# Converter_12V-5V.net
KiCad netlist of a schematic drawn in Altium Designer
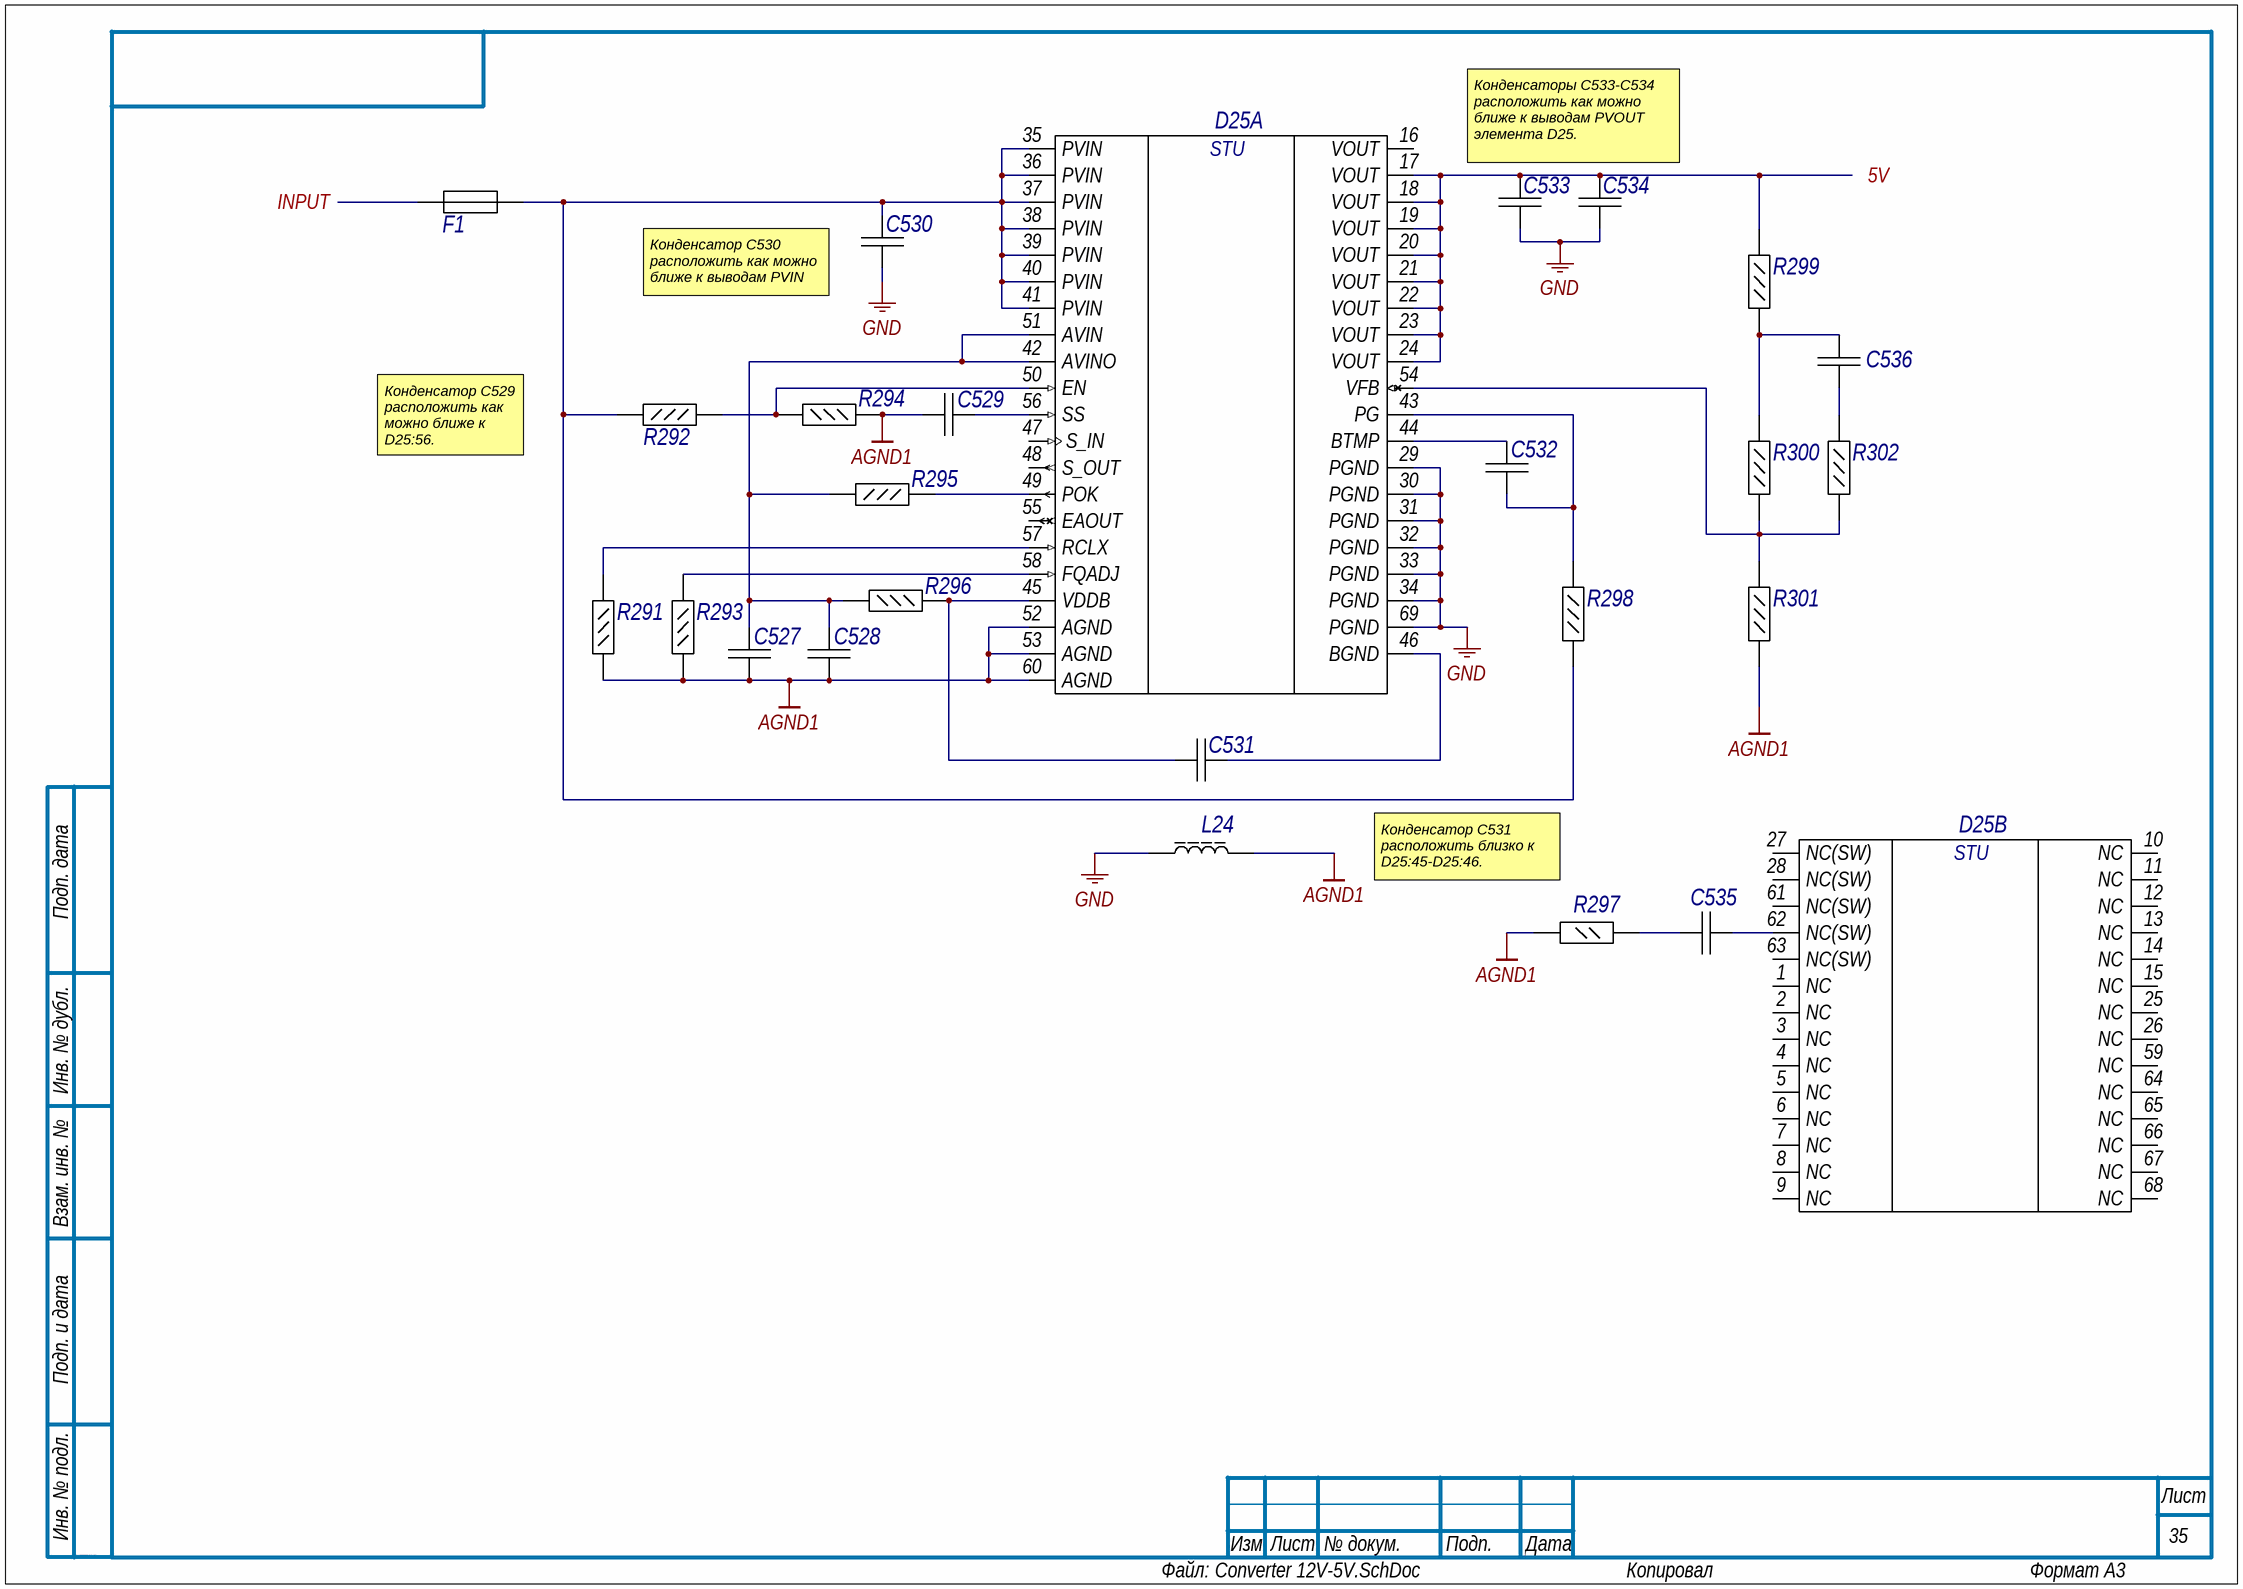
[diagram p0: Converter 12V-5V.SchDoc]

(export (version "E")
  (design (tool "Eeschema 10.0.6"))
  (components
    (comp (ref "C527")
      (value "CGB2A1X5R1E105K033BC")
      (footprint "CAPC1005X33X10LL5")
      (description "Chip Capacitor, 1 uF, +/- 10%, 25 V, -55 to 85 degC, 0402 (1005 Metric), RoHS, Tape and Reel")
      (fields (field (name "TOLERANCE") "10%"))
      (libsource (lib "MiniPC DB") (part "CAP_NP"))
    )
    (comp (ref "C528")
      (value "CGB2A1X5R1E105K033BC")
      (footprint "CAPC1005X33X10LL5")
      (description "Chip Capacitor, 1 uF, +/- 10%, 25 V, -55 to 85 degC, 0402 (1005 Metric), RoHS, Tape and Reel")
      (fields (field (name "TOLERANCE") "10%"))
      (libsource (lib "MiniPC DB") (part "CAP_NP"))
    )
    (comp (ref "C529")
      (value "GRM155R71E473KA88D")
      (footprint "CAPC1005X55X25NL05T10")
      (description "Chip Capacitor, 47 nF, +/- 10%, 25 V, -55 to 125 degC, 0402 (1005 Metric), RoHS, Tape and Reel")
      (fields (field (name "TOLERANCE") "10%") (field (name "MANUFACTURER") "Basic Passives"))
      (libsource (lib "MiniPC DB") (part "CAP_NP"))
    )
    (comp (ref "C530")
      (value "GRM31CR61E226KE15L")
      (footprint "CAPC3216X180X55ML20T25")
      (description "Chip Capacitor, 22 uF, +/- 10%, 25 V, -55 to 85 degC, 1206 (3216 Metric), RoHS, Tape and Reel")
      (fields (field (name "TOLERANCE") "10%"))
      (libsource (lib "MiniPC DB") (part "CAP_NP"))
    )
    (comp (ref "C531")
      (value "GRM155R61A224KE19D")
      (footprint "CAPC1005X55X25NL05T10")
      (description "Chip Capacitor, 220 nF, +/- 10%, 10 V, -55 to 85 degC, 0402 (1005 Metric), RoHS, Tape and Reel")
      (fields (field (name "TOLERANCE") "10%") (field (name "MANUFACTURER") "Basic Passives"))
      (libsource (lib "MiniPC DB") (part "CAP_NP"))
    )
    (comp (ref "C532")
      (value "GRM155R71E223KA61D")
      (footprint "CAPC1005X55X25ML05T10")
      (description "Chip Capacitor, 22 nF, +/- 10%, 25 V, -55 to 125 degC, 0402 (1005 Metric), RoHS, Tape and Reel")
      (fields (field (name "TOLERANCE") "10%") (field (name "MANUFACTURER") "Basic Passives"))
      (libsource (lib "MiniPC DB") (part "CAP_NP"))
    )
    (comp (ref "C533")
      (value "C3216X5R1A476M160AB")
      (footprint "CAPC3216X180X20ML20")
      (description "Chip Capacitor, 47 uF, +/- 20%, 10 V, -55 to 85 degC, 1206 (3216 Metric), RoHS, Tape and Reel")
      (fields (field (name "TOLERANCE") "20%"))
      (libsource (lib "MiniPC DB") (part "CAP_NP"))
    )
    (comp (ref "C534")
      (value "C3216X5R1A476M160AB")
      (footprint "CAPC3216X180X20ML20")
      (description "Chip Capacitor, 47 uF, +/- 20%, 10 V, -55 to 85 degC, 1206 (3216 Metric), RoHS, Tape and Reel")
      (fields (field (name "TOLERANCE") "20%"))
      (libsource (lib "MiniPC DB") (part "CAP_NP"))
    )
    (comp (ref "C535")
      (value "GRM155R71H681KA01D")
      (footprint "CAPC1005X55X25ML05T10")
      (description "Chip Capacitor, 680 pF, +/- 10%, 50 V, -55 to 125 degC, 0402 (1005 Metric), RoHS, Tape and Reel")
      (fields (field (name "TOLERANCE") "10%") (field (name "MANUFACTURER") "Basic Passives"))
      (libsource (lib "MiniPC DB") (part "CAP_NP"))
    )
    (comp (ref "C536")
      (value "GRM1535C1H560JDD5D")
      (footprint "CAPC1005X33X20ML05T10")
      (description "Chip Capacitor, 56 pF, +/- 5%, 50 V, -55 to 125 degC, 0402 (1005 Metric), RoHS, Tape and Reel")
      (fields (field (name "TOLERANCE") "5%") (field (name "MANUFACTURER") "Basic Passives"))
      (libsource (lib "MiniPC DB") (part "CAP_NP"))
    )
    (comp (ref "D25")
      (value "EN2342QI")
      (footprint "ALTR-QFN-68_A-305_D1-210_V")
      (libsource (lib "MiniPC DB") (part "EN2342QI"))
    )
    (comp (ref "F1")
      (value "154001")
      (footprint "LFUS-0154001.DR_V")
      (libsource (lib "MiniPC DB") (part "FUSE"))
    )
    (comp (ref "L24")
      (value "742792609")
      (footprint "SMD-0603")
      (description "SMD EMI Suppression Ferrite Bead WE-CBF, Z = 30 Ohm")
      (libsource (lib "MiniPC DB") (part "Choke"))
    )
    (comp (ref "R291")
      (value "ERJ-2RKF6812X")
      (footprint "RESC1005X40X25LL05T05")
      (description "Chip Resistor, 68.1 KOhm, +/- 1%, 100 mW, -55 to 155 degC, 0402 (1005 Metric), RoHS, Tape and Reel")
      (fields (field (name "TOLERANCE") "1%") (field (name "MANUFACTURER") "Basic Passives"))
      (libsource (lib "MiniPC DB") (part "RES-0.05"))
    )
    (comp (ref "R292")
      (value "ERJ-2RKF4992X")
      (footprint "RESC1005X40X25LL05T05")
      (description "Chip Resistor, 49.9 KOhm, +/- 1%, 100 mW, -55 to 155 degC, 0402 (1005 Metric), RoHS, Tape and Reel")
      (fields (field (name "TOLERANCE") "1%") (field (name "MANUFACTURER") "Basic Passives"))
      (libsource (lib "MiniPC DB") (part "RES-0.05"))
    )
    (comp (ref "R293")
      (value "CRCW040230K1FKED")
      (footprint "RESC1005X40X25LL05T05")
      (description "Chip Resistor, 30.1 KOhm, +/- 1%, 63 mW, -55 to 155 degC, 0402 (1005 Metric), RoHS, Tape and Reel")
      (fields (field (name "TOLERANCE") "1%") (field (name "MANUFACTURER") "Basic Passives"))
      (libsource (lib "MiniPC DB") (part "RES-0.05"))
    )
    (comp (ref "R294")
      (value "ERJ-2RKF1002X")
      (footprint "RESC1005X40X25LL05T05")
      (description "Chip Resistor, 10 KOhm, +/- 1%, 100 mW, -55 to 155 degC, 0402 (1005 Metric), RoHS, Tape and Reel")
      (fields (field (name "TOLERANCE") "1%") (field (name "MANUFACTURER") "Basic Passives"))
      (libsource (lib "") (part "RES-0.05_3"))
    )
    (comp (ref "R295")
      (value "ERJ-2RKF1003X")
      (footprint "RESC1005X40X25LL05T05")
      (description "Chip Resistor, 100 KOhm, +/- 1%, 100 mW, -55 to 155 degC, 0402 (1005 Metric), RoHS, Tape and Reel")
      (fields (field (name "TOLERANCE") "1%") (field (name "MANUFACTURER") "Basic Passives"))
      (libsource (lib "") (part "RES-0.05_2"))
    )
    (comp (ref "R296")
      (value "ERJ-2RKF4751X")
      (footprint "RESC1005X40X25LL05T05")
      (description "Chip Resistor, 4.75 KOhm, +/- 1%, 100 mW, -55 to 155 degC, 0402 (1005 Metric), RoHS, Tape and Reel")
      (fields (field (name "TOLERANCE") "1%") (field (name "MANUFACTURER") "Basic Passives"))
      (libsource (lib "") (part "RES-0.05_1"))
    )
    (comp (ref "R297")
      (value "ERJ-6RQF4R7V")
      (footprint "RESC2013X70X40LL20T20")
      (description "Chip Resistor, 4.7 Ohm, +/- 1%, 125 mW, -55 to 125 degC, 0805 (2012 Metric), RoHS, Tape and Reel")
      (fields (field (name "TOLERANCE") "1%"))
      (libsource (lib "MiniPC DB") (part "RES-0.125"))
    )
    (comp (ref "R298")
      (value "ERJ-2GEJ561x")
      (footprint "RESC1005X40X25LL05T05")
      (description "Chip Resistor, 560 Ohm, +/- 5%, 100 mW, -55 to 155 degC, 0402 (1005 Metric), RoHS, Tape and Reel")
      (fields (field (name "TOLERANCE") "5%") (field (name "MANUFACTURER") "Basic Passives"))
      (libsource (lib "") (part "RES-0.05_1"))
    )
    (comp (ref "R299")
      (value "ERJ-2GE0R00X")
      (footprint "RESC1005X40X25LL05T05")
      (description "Chip Resistor, 0 mOhm, +/- 5%, 100 mW, -55 to 155 degC, 0402 (1005 Metric), RoHS, Tape and Reel")
      (fields (field (name "TOLERANCE") "5%") (field (name "MANUFACTURER") "Basic Passives"))
      (libsource (lib "") (part "RES-0.05_1"))
    )
    (comp (ref "R300")
      (value "ERJ-2RKF8062X")
      (footprint "RESC1005X40X25LL05T05")
      (description "Chip Resistor, 80.6 KOhm, +/- 1%, 100 mW, -55 to 155 degC, 0402 (1005 Metric), RoHS, Tape and Reel")
      (fields (field (name "TOLERANCE") "1%") (field (name "MANUFACTURER") "Basic Passives"))
      (libsource (lib "") (part "RES-0.05_1"))
    )
    (comp (ref "R301")
      (value "ERJ-2RKF1432X")
      (footprint "RESC1005X40X25LL05T05")
      (description "Chip Resistor, 14.3 KOhm, +/- 1%, 100 mW, -55 to 155 degC, 0402 (1005 Metric), RoHS, Tape and Reel")
      (fields (field (name "TOLERANCE") "1%") (field (name "MANUFACTURER") "Basic Passives"))
      (libsource (lib "") (part "RES-0.05_1"))
    )
    (comp (ref "R302")
      (value "ERJ-2RKF1002X")
      (footprint "RESC1005X40X25LL05T05")
      (description "Chip Resistor, 10 KOhm, +/- 1%, 100 mW, -55 to 155 degC, 0402 (1005 Metric), RoHS, Tape and Reel")
      (fields (field (name "TOLERANCE") "1%") (field (name "MANUFACTURER") "Basic Passives"))
      (libsource (lib "") (part "RES-0.05_1"))
    )
  )
  (nets
    (net (code "1") (name "/5V") (class "Default")
      (node (ref "C533") (pin "2") (pinfunction "2_2") (pintype "passive"))
      (node (ref "C534") (pin "2") (pinfunction "2_2") (pintype "passive"))
      (node (ref "D25") (pin "17") (pinfunction "VOUT_17") (pintype "power_in"))
      (node (ref "D25") (pin "18") (pinfunction "VOUT_18") (pintype "power_in"))
      (node (ref "D25") (pin "19") (pinfunction "VOUT_19") (pintype "power_in"))
      (node (ref "D25") (pin "20") (pinfunction "VOUT_20") (pintype "power_in"))
      (node (ref "D25") (pin "21") (pinfunction "VOUT_21") (pintype "power_in"))
      (node (ref "D25") (pin "22") (pinfunction "VOUT_22") (pintype "power_in"))
      (node (ref "D25") (pin "23") (pinfunction "VOUT_23") (pintype "power_in"))
      (node (ref "D25") (pin "24") (pinfunction "VOUT_24") (pintype "power_in"))
      (node (ref "R299") (pin "2") (pinfunction "2_2") (pintype "passive"))
    )
    (net (code "2") (name "/INPUT") (class "Default")
      (node (ref "F1") (pin "2") (pinfunction "2_2") (pintype "passive"))
    )
    (net (code "3") (name "AGND1") (class "Default")
      (node (ref "C527") (pin "2") (pinfunction "2_2") (pintype "passive"))
      (node (ref "C528") (pin "1") (pinfunction "1_1") (pintype "passive"))
      (node (ref "C529") (pin "1") (pinfunction "1_1") (pintype "passive"))
      (node (ref "D25") (pin "52") (pinfunction "AGND_52") (pintype "power_in"))
      (node (ref "D25") (pin "53") (pinfunction "AGND_53") (pintype "power_in"))
      (node (ref "D25") (pin "60") (pinfunction "AGND_60") (pintype "power_in"))
      (node (ref "L24") (pin "2") (pinfunction "2_2") (pintype "passive"))
      (node (ref "R291") (pin "1") (pinfunction "1_1") (pintype "passive"))
      (node (ref "R293") (pin "1") (pinfunction "1_1") (pintype "passive"))
      (node (ref "R294") (pin "1") (pinfunction "1_1") (pintype "passive"))
      (node (ref "R297") (pin "1") (pinfunction "1_1") (pintype "passive"))
      (node (ref "R301") (pin "1") (pinfunction "1_1") (pintype "passive"))
    )
    (net (code "4") (name "GND") (class "Default")
      (node (ref "C530") (pin "1") (pinfunction "1_1") (pintype "passive"))
      (node (ref "C533") (pin "1") (pinfunction "1_1") (pintype "passive"))
      (node (ref "C534") (pin "1") (pinfunction "1_1") (pintype "passive"))
      (node (ref "D25") (pin "29") (pinfunction "PGND_29") (pintype "power_in"))
      (node (ref "D25") (pin "30") (pinfunction "PGND_30") (pintype "power_in"))
      (node (ref "D25") (pin "31") (pinfunction "PGND_31") (pintype "power_in"))
      (node (ref "D25") (pin "32") (pinfunction "PGND_32") (pintype "power_in"))
      (node (ref "D25") (pin "33") (pinfunction "PGND_33") (pintype "power_in"))
      (node (ref "D25") (pin "34") (pinfunction "PGND_34") (pintype "power_in"))
      (node (ref "D25") (pin "69") (pinfunction "PGND_69") (pintype "power_in"))
      (node (ref "L24") (pin "1") (pinfunction "1_1") (pintype "passive"))
    )
    (net (code "5") (name "Net-(C530-Pad2)") (class "Default")
      (node (ref "C530") (pin "2") (pinfunction "2_2") (pintype "passive"))
      (node (ref "D25") (pin "35") (pinfunction "PVIN_35") (pintype "power_in"))
      (node (ref "D25") (pin "36") (pinfunction "PVIN_36") (pintype "power_in"))
      (node (ref "D25") (pin "37") (pinfunction "PVIN_37") (pintype "power_in"))
      (node (ref "D25") (pin "38") (pinfunction "PVIN_38") (pintype "power_in"))
      (node (ref "D25") (pin "39") (pinfunction "PVIN_39") (pintype "power_in"))
      (node (ref "D25") (pin "40") (pinfunction "PVIN_40") (pintype "power_in"))
      (node (ref "D25") (pin "41") (pinfunction "PVIN_41") (pintype "power_in"))
      (node (ref "F1") (pin "1") (pinfunction "1_1") (pintype "passive"))
      (node (ref "R292") (pin "1") (pinfunction "1_1") (pintype "passive"))
      (node (ref "R298") (pin "1") (pinfunction "1_1") (pintype "passive"))
    )
    (net (code "6") (name "Net-(C535-Pad1)") (class "Default")
      (node (ref "C535") (pin "1") (pinfunction "1_1") (pintype "passive"))
      (node (ref "R297") (pin "2") (pinfunction "2_2") (pintype "passive"))
    )
    (net (code "7") (name "Net-(C535-Pad2)") (class "Default")
      (node (ref "C535") (pin "2") (pinfunction "2_2") (pintype "passive"))
      (node (ref "D25") (pin "62") (pinfunction "NC(SW)_62") (pintype "passive"))
    )
    (net (code "8") (name "Net-(C536-Pad1)") (class "Default")
      (node (ref "C536") (pin "1") (pinfunction "1_1") (pintype "passive"))
      (node (ref "R302") (pin "2") (pinfunction "2_2") (pintype "passive"))
    )
    (net (code "9") (name "Net-(C536-Pad2)") (class "Default")
      (node (ref "C536") (pin "2") (pinfunction "2_2") (pintype "passive"))
      (node (ref "R299") (pin "1") (pinfunction "1_1") (pintype "passive"))
      (node (ref "R300") (pin "2") (pinfunction "2_2") (pintype "passive"))
    )
    (net (code "10") (name "Net-(D25A-AVIN)") (class "Default")
      (node (ref "C527") (pin "1") (pinfunction "1_1") (pintype "passive"))
      (node (ref "C528") (pin "2") (pinfunction "2_2") (pintype "passive"))
      (node (ref "D25") (pin "42") (pinfunction "AVINO_42") (pintype "power_in"))
      (node (ref "D25") (pin "51") (pinfunction "AVIN_51") (pintype "power_in"))
      (node (ref "R295") (pin "2") (pinfunction "2_2") (pintype "passive"))
      (node (ref "R296") (pin "1") (pinfunction "1_1") (pintype "passive"))
    )
    (net (code "11") (name "Net-(D25A-BGND)") (class "Default")
      (node (ref "C531") (pin "1") (pinfunction "1_1") (pintype "passive"))
      (node (ref "D25") (pin "46") (pinfunction "BGND_46") (pintype "power_in"))
    )
    (net (code "12") (name "Net-(D25A-BTMP)") (class "Default")
      (node (ref "C532") (pin "1") (pinfunction "1_1") (pintype "passive"))
      (node (ref "D25") (pin "44") (pinfunction "BTMP_44") (pintype "power_in"))
    )
    (net (code "13") (name "Net-(D25A-EN)") (class "Default")
      (node (ref "D25") (pin "50") (pinfunction "EN_50") (pintype "input"))
      (node (ref "R292") (pin "2") (pinfunction "2_2") (pintype "passive"))
      (node (ref "R294") (pin "2") (pinfunction "2_2") (pintype "passive"))
    )
    (net (code "14") (name "Net-(D25A-FQADJ)") (class "Default")
      (node (ref "D25") (pin "58") (pinfunction "FQADJ_58") (pintype "input"))
      (node (ref "R293") (pin "2") (pinfunction "2_2") (pintype "passive"))
    )
    (net (code "15") (name "Net-(D25A-PG)") (class "Default")
      (node (ref "C532") (pin "2") (pinfunction "2_2") (pintype "passive"))
      (node (ref "D25") (pin "43") (pinfunction "PG_43") (pintype "passive"))
      (node (ref "R298") (pin "2") (pinfunction "2_2") (pintype "passive"))
    )
    (net (code "16") (name "Net-(D25A-POK)") (class "Default")
      (node (ref "D25") (pin "49") (pinfunction "POK_49") (pintype "open_collector"))
      (node (ref "R295") (pin "1") (pinfunction "1_1") (pintype "passive"))
    )
    (net (code "17") (name "Net-(D25A-RCLX)") (class "Default")
      (node (ref "D25") (pin "57") (pinfunction "RCLX_57") (pintype "input"))
      (node (ref "R291") (pin "2") (pinfunction "2_2") (pintype "passive"))
    )
    (net (code "18") (name "Net-(D25A-SS)") (class "Default")
      (node (ref "C529") (pin "2") (pinfunction "2_2") (pintype "passive"))
      (node (ref "D25") (pin "56") (pinfunction "SS_56") (pintype "input"))
    )
    (net (code "19") (name "Net-(D25A-VDDB)") (class "Default")
      (node (ref "C531") (pin "2") (pinfunction "2_2") (pintype "passive"))
      (node (ref "D25") (pin "45") (pinfunction "VDDB_45") (pintype "power_in"))
      (node (ref "R296") (pin "2") (pinfunction "2_2") (pintype "passive"))
    )
    (net (code "20") (name "Net-(D25A-VFB)") (class "Default")
      (node (ref "D25") (pin "54") (pinfunction "VFB_54") (pintype "input"))
      (node (ref "R300") (pin "1") (pinfunction "1_1") (pintype "passive"))
      (node (ref "R301") (pin "2") (pinfunction "2_2") (pintype "passive"))
      (node (ref "R302") (pin "1") (pinfunction "1_1") (pintype "passive"))
    )
    (net (code "21") (name "unconnected-(D25A-EAOUT-Pad55)") (class "Default")
      (node (ref "D25") (pin "55") (pinfunction "EAOUT_55") (pintype "output"))
    )
    (net (code "22") (name "unconnected-(D25A-S_IN-Pad47)") (class "Default")
      (node (ref "D25") (pin "47") (pinfunction "S_IN_47") (pintype "input"))
    )
    (net (code "23") (name "unconnected-(D25A-S_OUT-Pad48)") (class "Default")
      (node (ref "D25") (pin "48") (pinfunction "S_OUT_48") (pintype "output"))
    )
    (net (code "24") (name "unconnected-(D25A-VOUT-Pad16)") (class "Default")
      (node (ref "D25") (pin "16") (pinfunction "VOUT_16") (pintype "power_in"))
    )
    (net (code "25") (name "unconnected-(D25B-NC(SW)-Pad27)") (class "Default")
      (node (ref "D25") (pin "27") (pinfunction "NC(SW)_27") (pintype "passive"))
    )
    (net (code "26") (name "unconnected-(D25B-NC(SW)-Pad28)") (class "Default")
      (node (ref "D25") (pin "28") (pinfunction "NC(SW)_28") (pintype "passive"))
    )
    (net (code "27") (name "unconnected-(D25B-NC(SW)-Pad61)") (class "Default")
      (node (ref "D25") (pin "61") (pinfunction "NC(SW)_61") (pintype "passive"))
    )
    (net (code "28") (name "unconnected-(D25B-NC(SW)-Pad63)") (class "Default")
      (node (ref "D25") (pin "63") (pinfunction "NC(SW)_63") (pintype "passive"))
    )
    (net (code "29") (name "unconnected-(D25B-NC-Pad1)") (class "Default")
      (node (ref "D25") (pin "1") (pinfunction "NC_1") (pintype "passive"))
    )
    (net (code "30") (name "unconnected-(D25B-NC-Pad2)") (class "Default")
      (node (ref "D25") (pin "2") (pinfunction "NC_2") (pintype "passive"))
    )
    (net (code "31") (name "unconnected-(D25B-NC-Pad3)") (class "Default")
      (node (ref "D25") (pin "3") (pinfunction "NC_3") (pintype "passive"))
    )
    (net (code "32") (name "unconnected-(D25B-NC-Pad4)") (class "Default")
      (node (ref "D25") (pin "4") (pinfunction "NC_4") (pintype "passive"))
    )
    (net (code "33") (name "unconnected-(D25B-NC-Pad5)") (class "Default")
      (node (ref "D25") (pin "5") (pinfunction "NC_5") (pintype "passive"))
    )
    (net (code "34") (name "unconnected-(D25B-NC-Pad6)") (class "Default")
      (node (ref "D25") (pin "6") (pinfunction "NC_6") (pintype "passive"))
    )
    (net (code "35") (name "unconnected-(D25B-NC-Pad7)") (class "Default")
      (node (ref "D25") (pin "7") (pinfunction "NC_7") (pintype "passive"))
    )
    (net (code "36") (name "unconnected-(D25B-NC-Pad8)") (class "Default")
      (node (ref "D25") (pin "8") (pinfunction "NC_8") (pintype "passive"))
    )
    (net (code "37") (name "unconnected-(D25B-NC-Pad9)") (class "Default")
      (node (ref "D25") (pin "9") (pinfunction "NC_9") (pintype "passive"))
    )
    (net (code "38") (name "unconnected-(D25B-NC-Pad10)") (class "Default")
      (node (ref "D25") (pin "10") (pinfunction "NC_10") (pintype "passive"))
    )
    (net (code "39") (name "unconnected-(D25B-NC-Pad11)") (class "Default")
      (node (ref "D25") (pin "11") (pinfunction "NC_11") (pintype "passive"))
    )
    (net (code "40") (name "unconnected-(D25B-NC-Pad12)") (class "Default")
      (node (ref "D25") (pin "12") (pinfunction "NC_12") (pintype "passive"))
    )
    (net (code "41") (name "unconnected-(D25B-NC-Pad13)") (class "Default")
      (node (ref "D25") (pin "13") (pinfunction "NC_13") (pintype "passive"))
    )
    (net (code "42") (name "unconnected-(D25B-NC-Pad14)") (class "Default")
      (node (ref "D25") (pin "14") (pinfunction "NC_14") (pintype "passive"))
    )
    (net (code "43") (name "unconnected-(D25B-NC-Pad15)") (class "Default")
      (node (ref "D25") (pin "15") (pinfunction "NC_15") (pintype "passive"))
    )
    (net (code "44") (name "unconnected-(D25B-NC-Pad25)") (class "Default")
      (node (ref "D25") (pin "25") (pinfunction "NC_25") (pintype "passive"))
    )
    (net (code "45") (name "unconnected-(D25B-NC-Pad26)") (class "Default")
      (node (ref "D25") (pin "26") (pinfunction "NC_26") (pintype "passive"))
    )
    (net (code "46") (name "unconnected-(D25B-NC-Pad59)") (class "Default")
      (node (ref "D25") (pin "59") (pinfunction "NC_59") (pintype "passive"))
    )
    (net (code "47") (name "unconnected-(D25B-NC-Pad64)") (class "Default")
      (node (ref "D25") (pin "64") (pinfunction "NC_64") (pintype "passive"))
    )
    (net (code "48") (name "unconnected-(D25B-NC-Pad65)") (class "Default")
      (node (ref "D25") (pin "65") (pinfunction "NC_65") (pintype "passive"))
    )
    (net (code "49") (name "unconnected-(D25B-NC-Pad66)") (class "Default")
      (node (ref "D25") (pin "66") (pinfunction "NC_66") (pintype "passive"))
    )
    (net (code "50") (name "unconnected-(D25B-NC-Pad67)") (class "Default")
      (node (ref "D25") (pin "67") (pinfunction "NC_67") (pintype "passive"))
    )
    (net (code "51") (name "unconnected-(D25B-NC-Pad68)") (class "Default")
      (node (ref "D25") (pin "68") (pinfunction "NC_68") (pintype "passive"))
    )
  )
)
